# stereo_mix_front.net
KiCad netlist of a schematic drawn in EAGLE
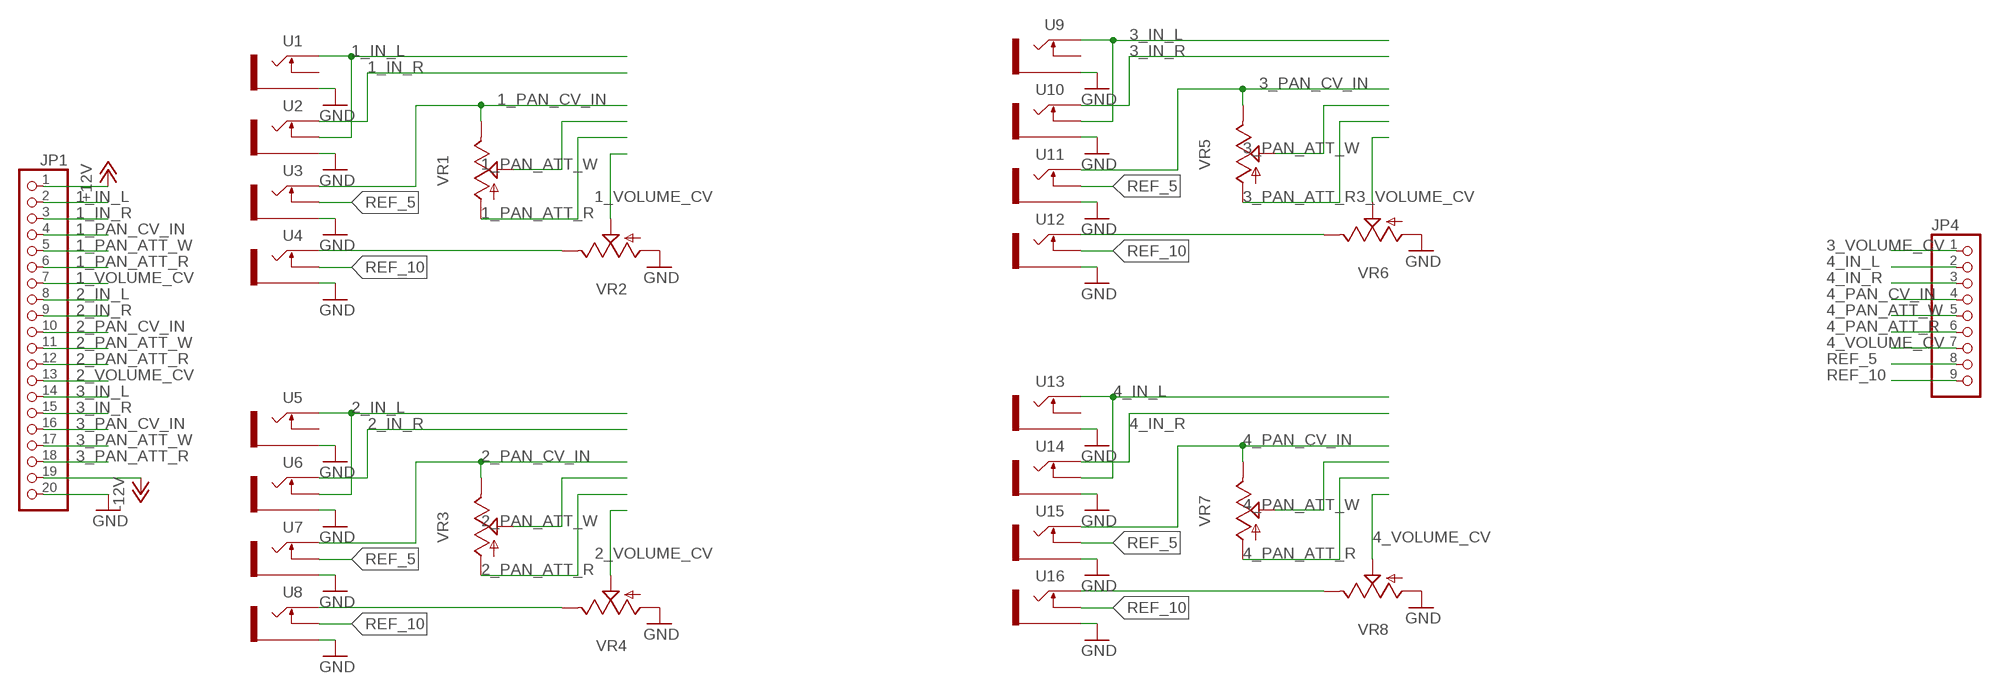
[diagram p0: schematic, sheet 1]
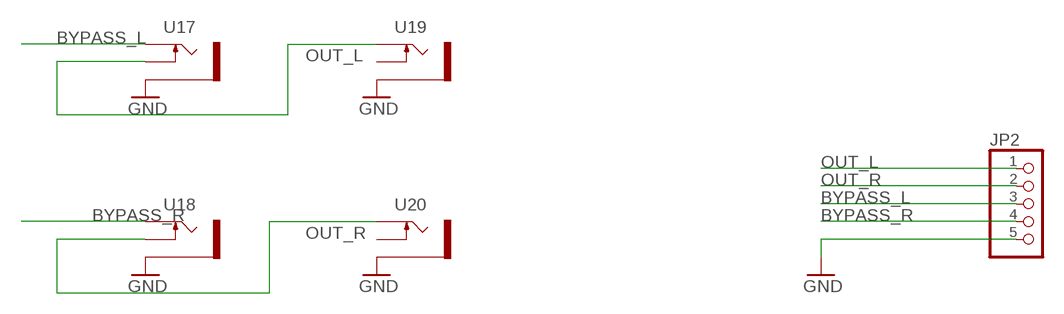
[diagram p1: schematic, sheet 2]

(export (version "E")
  (design (tool "Eeschema 10.0.6"))
  (components
    (comp (ref "JP1")
      (value "PINHD-1X20")
      (footprint "eagle-import:1X20")
      (libsource (lib "eagle-import") (part "PINHD-1X20"))
    )
    (comp (ref "JP4")
      (value "PINHD-1X9")
      (footprint "eagle-import:1X09")
      (libsource (lib "eagle-import") (part "PINHD-1X9"))
    )
    (comp (ref "U1")
      (value "THONKICONNOLD")
      (footprint "eagle-import:THONKICONN")
      (libsource (lib "eagle-import") (part "THONKICONNOLD"))
    )
    (comp (ref "U2")
      (value "THONKICONNOLD")
      (footprint "eagle-import:THONKICONN")
      (libsource (lib "eagle-import") (part "THONKICONNOLD"))
    )
    (comp (ref "U3")
      (value "THONKICONNOLD")
      (footprint "eagle-import:THONKICONN")
      (libsource (lib "eagle-import") (part "THONKICONNOLD"))
    )
    (comp (ref "U4")
      (value "THONKICONNOLD")
      (footprint "eagle-import:THONKICONN")
      (libsource (lib "eagle-import") (part "THONKICONNOLD"))
    )
    (comp (ref "U5")
      (value "THONKICONNOLD")
      (footprint "eagle-import:THONKICONN")
      (libsource (lib "eagle-import") (part "THONKICONNOLD"))
    )
    (comp (ref "U6")
      (value "THONKICONNOLD")
      (footprint "eagle-import:THONKICONN")
      (libsource (lib "eagle-import") (part "THONKICONNOLD"))
    )
    (comp (ref "U7")
      (value "THONKICONNOLD")
      (footprint "eagle-import:THONKICONN")
      (libsource (lib "eagle-import") (part "THONKICONNOLD"))
    )
    (comp (ref "U8")
      (value "THONKICONNOLD")
      (footprint "eagle-import:THONKICONN")
      (libsource (lib "eagle-import") (part "THONKICONNOLD"))
    )
    (comp (ref "U9")
      (value "THONKICONNOLD")
      (footprint "eagle-import:THONKICONN")
      (libsource (lib "eagle-import") (part "THONKICONNOLD"))
    )
    (comp (ref "U10")
      (value "THONKICONNOLD")
      (footprint "eagle-import:THONKICONN")
      (libsource (lib "eagle-import") (part "THONKICONNOLD"))
    )
    (comp (ref "U11")
      (value "THONKICONNOLD")
      (footprint "eagle-import:THONKICONN")
      (libsource (lib "eagle-import") (part "THONKICONNOLD"))
    )
    (comp (ref "U12")
      (value "THONKICONNOLD")
      (footprint "eagle-import:THONKICONN")
      (libsource (lib "eagle-import") (part "THONKICONNOLD"))
    )
    (comp (ref "U13")
      (value "THONKICONNOLD")
      (footprint "eagle-import:THONKICONN")
      (libsource (lib "eagle-import") (part "THONKICONNOLD"))
    )
    (comp (ref "U14")
      (value "THONKICONNOLD")
      (footprint "eagle-import:THONKICONN")
      (libsource (lib "eagle-import") (part "THONKICONNOLD"))
    )
    (comp (ref "U15")
      (value "THONKICONNOLD")
      (footprint "eagle-import:THONKICONN")
      (libsource (lib "eagle-import") (part "THONKICONNOLD"))
    )
    (comp (ref "U16")
      (value "THONKICONNOLD")
      (footprint "eagle-import:THONKICONN")
      (libsource (lib "eagle-import") (part "THONKICONNOLD"))
    )
    (comp (ref "VR1")
      (value "9MM_SNAP-IN_POT_")
      (footprint "eagle-import:9MM_SNAP-IN_POT")
      (fields (field (name "SPICEPREFIX") "J"))
      (libsource (lib "eagle-import") (part "9MM_SNAP-IN_POT_"))
    )
    (comp (ref "VR2")
      (value "9MM_SNAP-IN_POT_")
      (footprint "eagle-import:9MM_SNAP-IN_POT")
      (fields (field (name "SPICEPREFIX") "J"))
      (libsource (lib "eagle-import") (part "9MM_SNAP-IN_POT_"))
    )
    (comp (ref "VR3")
      (value "9MM_SNAP-IN_POT_")
      (footprint "eagle-import:9MM_SNAP-IN_POT")
      (fields (field (name "SPICEPREFIX") "J"))
      (libsource (lib "eagle-import") (part "9MM_SNAP-IN_POT_"))
    )
    (comp (ref "VR4")
      (value "9MM_SNAP-IN_POT_")
      (footprint "eagle-import:9MM_SNAP-IN_POT")
      (fields (field (name "SPICEPREFIX") "J"))
      (libsource (lib "eagle-import") (part "9MM_SNAP-IN_POT_"))
    )
    (comp (ref "VR5")
      (value "9MM_SNAP-IN_POT_")
      (footprint "eagle-import:9MM_SNAP-IN_POT")
      (fields (field (name "SPICEPREFIX") "J"))
      (libsource (lib "eagle-import") (part "9MM_SNAP-IN_POT_"))
    )
    (comp (ref "VR6")
      (value "9MM_SNAP-IN_POT_")
      (footprint "eagle-import:9MM_SNAP-IN_POT")
      (fields (field (name "SPICEPREFIX") "J"))
      (libsource (lib "eagle-import") (part "9MM_SNAP-IN_POT_"))
    )
    (comp (ref "VR7")
      (value "9MM_SNAP-IN_POT_")
      (footprint "eagle-import:9MM_SNAP-IN_POT")
      (fields (field (name "SPICEPREFIX") "J"))
      (libsource (lib "eagle-import") (part "9MM_SNAP-IN_POT_"))
    )
    (comp (ref "VR8")
      (value "9MM_SNAP-IN_POT_")
      (footprint "eagle-import:9MM_SNAP-IN_POT")
      (fields (field (name "SPICEPREFIX") "J"))
      (libsource (lib "eagle-import") (part "9MM_SNAP-IN_POT_"))
    )
    (comp (ref "JP2")
      (value "PINHD-1X5")
      (footprint "eagle-import:1X05")
      (libsource (lib "eagle-import") (part "PINHD-1X5"))
    )
    (comp (ref "U17")
      (value "THONKICONNOLD")
      (footprint "eagle-import:THONKICONN")
      (libsource (lib "eagle-import") (part "THONKICONNOLD"))
    )
    (comp (ref "U18")
      (value "THONKICONNOLD")
      (footprint "eagle-import:THONKICONN")
      (libsource (lib "eagle-import") (part "THONKICONNOLD"))
    )
    (comp (ref "U19")
      (value "THONKICONNOLD")
      (footprint "eagle-import:THONKICONN")
      (libsource (lib "eagle-import") (part "THONKICONNOLD"))
    )
    (comp (ref "U20")
      (value "THONKICONNOLD")
      (footprint "eagle-import:THONKICONN")
      (libsource (lib "eagle-import") (part "THONKICONNOLD"))
    )
  )
  (nets
    (net (code "1") (name "+12V") (class "Default")
      (node (ref "JP1") (pin "1") (pinfunction "1_1") (pintype "passive"))
    )
    (net (code "2") (name "-12V") (class "Default")
      (node (ref "JP1") (pin "19") (pinfunction "19_19") (pintype "passive"))
    )
    (net (code "3") (name "1_IN_L") (class "Default")
      (node (ref "JP1") (pin "2") (pinfunction "2_2") (pintype "passive"))
      (node (ref "U1") (pin "P$3_TIP") (pinfunction "TIP_P$3_TIP") (pintype "passive"))
      (node (ref "U2") (pin "P$2_SWITCH") (pinfunction "SWITCH_P$2_SWITCH") (pintype "passive"))
    )
    (net (code "4") (name "1_IN_R") (class "Default")
      (node (ref "JP1") (pin "3") (pinfunction "3_3") (pintype "passive"))
      (node (ref "U2") (pin "P$3_TIP") (pinfunction "TIP_P$3_TIP") (pintype "passive"))
    )
    (net (code "5") (name "1_PAN_ATT_R") (class "Default")
      (node (ref "JP1") (pin "6") (pinfunction "6_6") (pintype "passive"))
      (node (ref "VR1") (pin "1") (pinfunction "A_1") (pintype "passive"))
    )
    (net (code "6") (name "1_PAN_ATT_W") (class "Default")
      (node (ref "JP1") (pin "5") (pinfunction "5_5") (pintype "passive"))
      (node (ref "VR1") (pin "2") (pinfunction "S_2") (pintype "passive"))
    )
    (net (code "7") (name "1_PAN_CV_IN") (class "Default")
      (node (ref "JP1") (pin "4") (pinfunction "4_4") (pintype "passive"))
      (node (ref "U3") (pin "P$3_TIP") (pinfunction "TIP_P$3_TIP") (pintype "passive"))
      (node (ref "VR1") (pin "3") (pinfunction "E_3") (pintype "passive"))
    )
    (net (code "8") (name "1_VOLUME_CV") (class "Default")
      (node (ref "JP1") (pin "7") (pinfunction "7_7") (pintype "passive"))
      (node (ref "VR2") (pin "2") (pinfunction "S_2") (pintype "passive"))
    )
    (net (code "9") (name "2_IN_L") (class "Default")
      (node (ref "JP1") (pin "8") (pinfunction "8_8") (pintype "passive"))
      (node (ref "U5") (pin "P$3_TIP") (pinfunction "TIP_P$3_TIP") (pintype "passive"))
      (node (ref "U6") (pin "P$2_SWITCH") (pinfunction "SWITCH_P$2_SWITCH") (pintype "passive"))
    )
    (net (code "10") (name "2_IN_R") (class "Default")
      (node (ref "JP1") (pin "9") (pinfunction "9_9") (pintype "passive"))
      (node (ref "U6") (pin "P$3_TIP") (pinfunction "TIP_P$3_TIP") (pintype "passive"))
    )
    (net (code "11") (name "2_PAN_ATT_R") (class "Default")
      (node (ref "JP1") (pin "12") (pinfunction "12_12") (pintype "passive"))
      (node (ref "VR3") (pin "1") (pinfunction "A_1") (pintype "passive"))
    )
    (net (code "12") (name "2_PAN_ATT_W") (class "Default")
      (node (ref "JP1") (pin "11") (pinfunction "11_11") (pintype "passive"))
      (node (ref "VR3") (pin "2") (pinfunction "S_2") (pintype "passive"))
    )
    (net (code "13") (name "2_PAN_CV_IN") (class "Default")
      (node (ref "JP1") (pin "10") (pinfunction "10_10") (pintype "passive"))
      (node (ref "U7") (pin "P$3_TIP") (pinfunction "TIP_P$3_TIP") (pintype "passive"))
      (node (ref "VR3") (pin "3") (pinfunction "E_3") (pintype "passive"))
    )
    (net (code "14") (name "2_VOLUME_CV") (class "Default")
      (node (ref "JP1") (pin "13") (pinfunction "13_13") (pintype "passive"))
      (node (ref "VR4") (pin "2") (pinfunction "S_2") (pintype "passive"))
    )
    (net (code "15") (name "3_IN_L") (class "Default")
      (node (ref "JP1") (pin "14") (pinfunction "14_14") (pintype "passive"))
      (node (ref "U10") (pin "P$2_SWITCH") (pinfunction "SWITCH_P$2_SWITCH") (pintype "passive"))
      (node (ref "U9") (pin "P$3_TIP") (pinfunction "TIP_P$3_TIP") (pintype "passive"))
    )
    (net (code "16") (name "3_IN_R") (class "Default")
      (node (ref "JP1") (pin "15") (pinfunction "15_15") (pintype "passive"))
      (node (ref "U10") (pin "P$3_TIP") (pinfunction "TIP_P$3_TIP") (pintype "passive"))
    )
    (net (code "17") (name "3_PAN_ATT_R") (class "Default")
      (node (ref "JP1") (pin "18") (pinfunction "18_18") (pintype "passive"))
      (node (ref "VR5") (pin "1") (pinfunction "A_1") (pintype "passive"))
    )
    (net (code "18") (name "3_PAN_ATT_W") (class "Default")
      (node (ref "JP1") (pin "17") (pinfunction "17_17") (pintype "passive"))
      (node (ref "VR5") (pin "2") (pinfunction "S_2") (pintype "passive"))
    )
    (net (code "19") (name "3_PAN_CV_IN") (class "Default")
      (node (ref "JP1") (pin "16") (pinfunction "16_16") (pintype "passive"))
      (node (ref "U11") (pin "P$3_TIP") (pinfunction "TIP_P$3_TIP") (pintype "passive"))
      (node (ref "VR5") (pin "3") (pinfunction "E_3") (pintype "passive"))
    )
    (net (code "20") (name "3_VOLUME_CV") (class "Default")
      (node (ref "JP4") (pin "1") (pinfunction "1_1") (pintype "passive"))
      (node (ref "VR6") (pin "2") (pinfunction "S_2") (pintype "passive"))
    )
    (net (code "21") (name "4_IN_L") (class "Default")
      (node (ref "JP4") (pin "2") (pinfunction "2_2") (pintype "passive"))
      (node (ref "U13") (pin "P$3_TIP") (pinfunction "TIP_P$3_TIP") (pintype "passive"))
      (node (ref "U14") (pin "P$2_SWITCH") (pinfunction "SWITCH_P$2_SWITCH") (pintype "passive"))
    )
    (net (code "22") (name "4_IN_R") (class "Default")
      (node (ref "JP4") (pin "3") (pinfunction "3_3") (pintype "passive"))
      (node (ref "U14") (pin "P$3_TIP") (pinfunction "TIP_P$3_TIP") (pintype "passive"))
    )
    (net (code "23") (name "4_PAN_ATT_R") (class "Default")
      (node (ref "JP4") (pin "6") (pinfunction "6_6") (pintype "passive"))
      (node (ref "VR7") (pin "1") (pinfunction "A_1") (pintype "passive"))
    )
    (net (code "24") (name "4_PAN_ATT_W") (class "Default")
      (node (ref "JP4") (pin "5") (pinfunction "5_5") (pintype "passive"))
      (node (ref "VR7") (pin "2") (pinfunction "S_2") (pintype "passive"))
    )
    (net (code "25") (name "4_PAN_CV_IN") (class "Default")
      (node (ref "JP4") (pin "4") (pinfunction "4_4") (pintype "passive"))
      (node (ref "U15") (pin "P$3_TIP") (pinfunction "TIP_P$3_TIP") (pintype "passive"))
      (node (ref "VR7") (pin "3") (pinfunction "E_3") (pintype "passive"))
    )
    (net (code "26") (name "4_VOLUME_CV") (class "Default")
      (node (ref "JP4") (pin "7") (pinfunction "7_7") (pintype "passive"))
      (node (ref "VR8") (pin "2") (pinfunction "S_2") (pintype "passive"))
    )
    (net (code "27") (name "BYPASS_L") (class "Default")
      (node (ref "JP2") (pin "3") (pinfunction "3_3") (pintype "passive"))
      (node (ref "U17") (pin "P$3_TIP") (pinfunction "TIP_P$3_TIP") (pintype "passive"))
    )
    (net (code "28") (name "BYPASS_R") (class "Default")
      (node (ref "JP2") (pin "4") (pinfunction "4_4") (pintype "passive"))
      (node (ref "U18") (pin "P$3_TIP") (pinfunction "TIP_P$3_TIP") (pintype "passive"))
    )
    (net (code "29") (name "GND") (class "Default")
      (node (ref "JP1") (pin "20") (pinfunction "20_20") (pintype "passive"))
      (node (ref "JP2") (pin "5") (pinfunction "5_5") (pintype "passive"))
      (node (ref "U1") (pin "P$1_SLEEVE") (pinfunction "SLEEVE_P$1_SLEEVE") (pintype "passive"))
      (node (ref "U10") (pin "P$1_SLEEVE") (pinfunction "SLEEVE_P$1_SLEEVE") (pintype "passive"))
      (node (ref "U11") (pin "P$1_SLEEVE") (pinfunction "SLEEVE_P$1_SLEEVE") (pintype "passive"))
      (node (ref "U12") (pin "P$1_SLEEVE") (pinfunction "SLEEVE_P$1_SLEEVE") (pintype "passive"))
      (node (ref "U13") (pin "P$1_SLEEVE") (pinfunction "SLEEVE_P$1_SLEEVE") (pintype "passive"))
      (node (ref "U14") (pin "P$1_SLEEVE") (pinfunction "SLEEVE_P$1_SLEEVE") (pintype "passive"))
      (node (ref "U15") (pin "P$1_SLEEVE") (pinfunction "SLEEVE_P$1_SLEEVE") (pintype "passive"))
      (node (ref "U16") (pin "P$1_SLEEVE") (pinfunction "SLEEVE_P$1_SLEEVE") (pintype "passive"))
      (node (ref "U17") (pin "P$1_SLEEVE") (pinfunction "SLEEVE_P$1_SLEEVE") (pintype "passive"))
      (node (ref "U18") (pin "P$1_SLEEVE") (pinfunction "SLEEVE_P$1_SLEEVE") (pintype "passive"))
      (node (ref "U19") (pin "P$1_SLEEVE") (pinfunction "SLEEVE_P$1_SLEEVE") (pintype "passive"))
      (node (ref "U2") (pin "P$1_SLEEVE") (pinfunction "SLEEVE_P$1_SLEEVE") (pintype "passive"))
      (node (ref "U20") (pin "P$1_SLEEVE") (pinfunction "SLEEVE_P$1_SLEEVE") (pintype "passive"))
      (node (ref "U3") (pin "P$1_SLEEVE") (pinfunction "SLEEVE_P$1_SLEEVE") (pintype "passive"))
      (node (ref "U4") (pin "P$1_SLEEVE") (pinfunction "SLEEVE_P$1_SLEEVE") (pintype "passive"))
      (node (ref "U5") (pin "P$1_SLEEVE") (pinfunction "SLEEVE_P$1_SLEEVE") (pintype "passive"))
      (node (ref "U6") (pin "P$1_SLEEVE") (pinfunction "SLEEVE_P$1_SLEEVE") (pintype "passive"))
      (node (ref "U7") (pin "P$1_SLEEVE") (pinfunction "SLEEVE_P$1_SLEEVE") (pintype "passive"))
      (node (ref "U8") (pin "P$1_SLEEVE") (pinfunction "SLEEVE_P$1_SLEEVE") (pintype "passive"))
      (node (ref "U9") (pin "P$1_SLEEVE") (pinfunction "SLEEVE_P$1_SLEEVE") (pintype "passive"))
      (node (ref "VR2") (pin "1") (pinfunction "A_1") (pintype "passive"))
      (node (ref "VR4") (pin "1") (pinfunction "A_1") (pintype "passive"))
      (node (ref "VR6") (pin "1") (pinfunction "A_1") (pintype "passive"))
      (node (ref "VR8") (pin "1") (pinfunction "A_1") (pintype "passive"))
    )
    (net (code "30") (name "Net-(U4-TIP)") (class "Default")
      (node (ref "U4") (pin "P$3_TIP") (pinfunction "TIP_P$3_TIP") (pintype "passive"))
      (node (ref "VR2") (pin "3") (pinfunction "E_3") (pintype "passive"))
    )
    (net (code "31") (name "Net-(U8-TIP)") (class "Default")
      (node (ref "U8") (pin "P$3_TIP") (pinfunction "TIP_P$3_TIP") (pintype "passive"))
      (node (ref "VR4") (pin "3") (pinfunction "E_3") (pintype "passive"))
    )
    (net (code "32") (name "Net-(U12-TIP)") (class "Default")
      (node (ref "U12") (pin "P$3_TIP") (pinfunction "TIP_P$3_TIP") (pintype "passive"))
      (node (ref "VR6") (pin "3") (pinfunction "E_3") (pintype "passive"))
    )
    (net (code "33") (name "Net-(U16-TIP)") (class "Default")
      (node (ref "U16") (pin "P$3_TIP") (pinfunction "TIP_P$3_TIP") (pintype "passive"))
      (node (ref "VR8") (pin "3") (pinfunction "E_3") (pintype "passive"))
    )
    (net (code "34") (name "OUT_L") (class "Default")
      (node (ref "JP2") (pin "1") (pinfunction "1_1") (pintype "passive"))
      (node (ref "U17") (pin "P$2_SWITCH") (pinfunction "SWITCH_P$2_SWITCH") (pintype "passive"))
      (node (ref "U19") (pin "P$3_TIP") (pinfunction "TIP_P$3_TIP") (pintype "passive"))
    )
    (net (code "35") (name "OUT_R") (class "Default")
      (node (ref "JP2") (pin "2") (pinfunction "2_2") (pintype "passive"))
      (node (ref "U18") (pin "P$2_SWITCH") (pinfunction "SWITCH_P$2_SWITCH") (pintype "passive"))
      (node (ref "U20") (pin "P$3_TIP") (pinfunction "TIP_P$3_TIP") (pintype "passive"))
    )
    (net (code "36") (name "REF_5") (class "Default")
      (node (ref "JP4") (pin "8") (pinfunction "8_8") (pintype "passive"))
      (node (ref "U11") (pin "P$2_SWITCH") (pinfunction "SWITCH_P$2_SWITCH") (pintype "passive"))
      (node (ref "U15") (pin "P$2_SWITCH") (pinfunction "SWITCH_P$2_SWITCH") (pintype "passive"))
      (node (ref "U3") (pin "P$2_SWITCH") (pinfunction "SWITCH_P$2_SWITCH") (pintype "passive"))
      (node (ref "U7") (pin "P$2_SWITCH") (pinfunction "SWITCH_P$2_SWITCH") (pintype "passive"))
    )
    (net (code "37") (name "REF_10") (class "Default")
      (node (ref "JP4") (pin "9") (pinfunction "9_9") (pintype "passive"))
      (node (ref "U12") (pin "P$2_SWITCH") (pinfunction "SWITCH_P$2_SWITCH") (pintype "passive"))
      (node (ref "U16") (pin "P$2_SWITCH") (pinfunction "SWITCH_P$2_SWITCH") (pintype "passive"))
      (node (ref "U4") (pin "P$2_SWITCH") (pinfunction "SWITCH_P$2_SWITCH") (pintype "passive"))
      (node (ref "U8") (pin "P$2_SWITCH") (pinfunction "SWITCH_P$2_SWITCH") (pintype "passive"))
    )
    (net (code "38") (name "unconnected-(U1-SWITCH-PadP$2_SWITCH)") (class "Default")
      (node (ref "U1") (pin "P$2_SWITCH") (pinfunction "SWITCH_P$2_SWITCH") (pintype "passive"))
    )
    (net (code "39") (name "unconnected-(U5-SWITCH-PadP$2_SWITCH)") (class "Default")
      (node (ref "U5") (pin "P$2_SWITCH") (pinfunction "SWITCH_P$2_SWITCH") (pintype "passive"))
    )
    (net (code "40") (name "unconnected-(U9-SWITCH-PadP$2_SWITCH)") (class "Default")
      (node (ref "U9") (pin "P$2_SWITCH") (pinfunction "SWITCH_P$2_SWITCH") (pintype "passive"))
    )
    (net (code "41") (name "unconnected-(U13-SWITCH-PadP$2_SWITCH)") (class "Default")
      (node (ref "U13") (pin "P$2_SWITCH") (pinfunction "SWITCH_P$2_SWITCH") (pintype "passive"))
    )
    (net (code "42") (name "unconnected-(U19-SWITCH-PadP$2_SWITCH)") (class "Default")
      (node (ref "U19") (pin "P$2_SWITCH") (pinfunction "SWITCH_P$2_SWITCH") (pintype "passive"))
    )
    (net (code "43") (name "unconnected-(U20-SWITCH-PadP$2_SWITCH)") (class "Default")
      (node (ref "U20") (pin "P$2_SWITCH") (pinfunction "SWITCH_P$2_SWITCH") (pintype "passive"))
    )
  )
)
